# 0123-chips-test-pcb-01.net
KiCad netlist of a schematic drawn in EAGLE
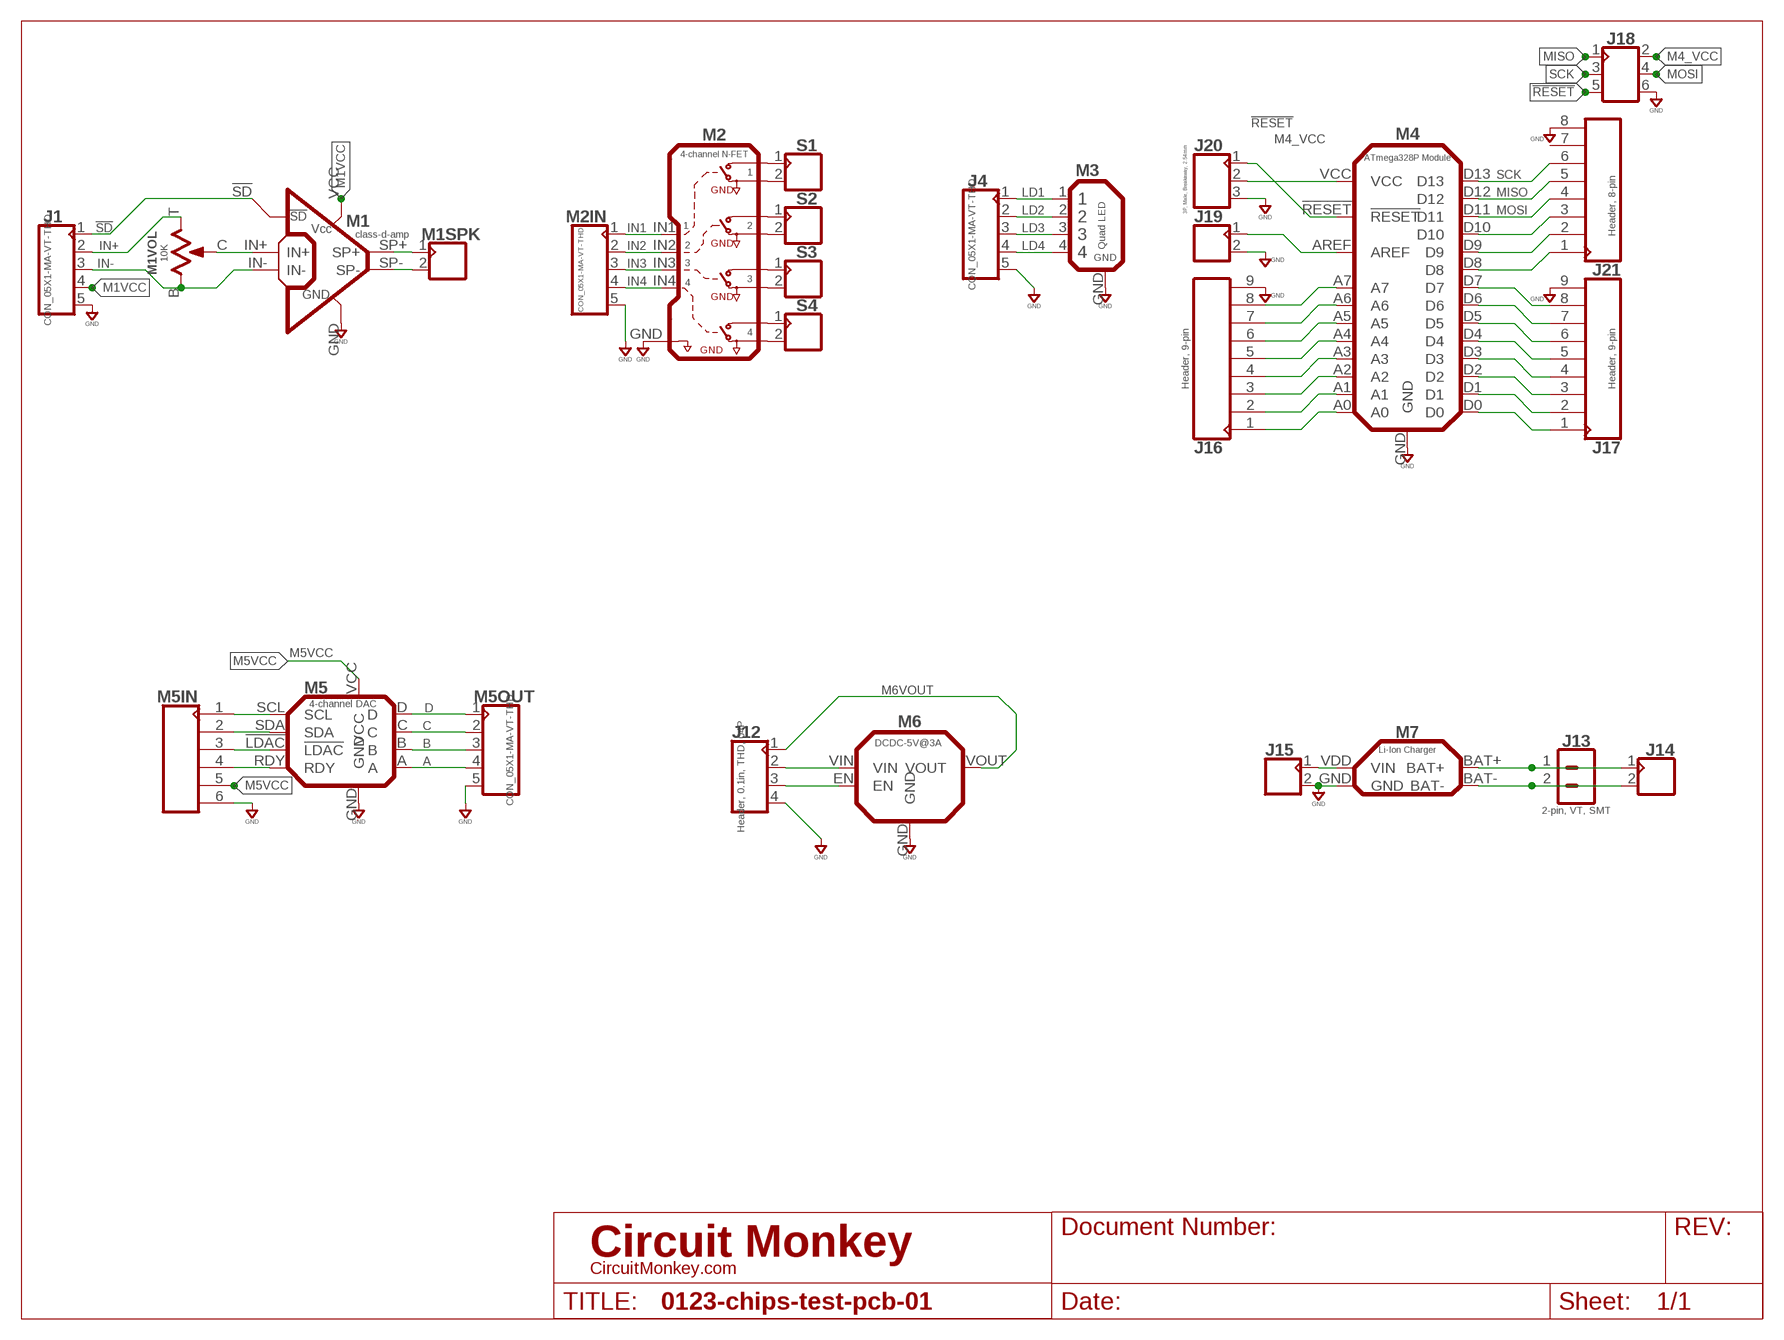
[diagram p0: schematic, sheet 1]

(export (version "E")
  (design (tool "Eeschema 10.0.6"))
  (components
    (comp (ref "J1")
      (value "CON_05X1-MA-VT-THD")
      (footprint "eagle-import:MA05X1-VT-THD")
      (libsource (lib "eagle-import") (part "CON_05X1-MA-VT-THD"))
    )
    (comp (ref "J4")
      (value "CON_05X1-MA-VT-THD")
      (footprint "eagle-import:MA05X1-VT-THD")
      (libsource (lib "eagle-import") (part "CON_05X1-MA-VT-THD"))
    )
    (comp (ref "J12")
      (value "Header, 0.1in, THD, 04P")
      (footprint "eagle-import:MA04X1-VT-THD")
      (fields (field (name "MFR") "Molex") (field (name "MPN") "022284043"))
      (libsource (lib "eagle-import") (part "CON_04X1-THD-VT"))
    )
    (comp (ref "J13")
      (value "2-pin, VT, SMT")
      (footprint "eagle-import:B2B-PH-SM4")
      (fields (field (name "MFR") "JST") (field (name "MPN") "B2B-PH-SM4"))
      (libsource (lib "eagle-import") (part "02PVT-SMT"))
    )
    (comp (ref "J14")
      (value "CON_02X1-2.54MM-THD-VT")
      (footprint "eagle-import:MA02X1-VT-THD")
      (libsource (lib "eagle-import") (part "CON_02X1-2.54MM-THD-VT"))
    )
    (comp (ref "J15")
      (value "CON_02X1-2.54MM-THD-VT")
      (footprint "eagle-import:MA02X1-VT-THD")
      (libsource (lib "eagle-import") (part "CON_02X1-2.54MM-THD-VT"))
    )
    (comp (ref "J16")
      (value "Header, 9-pin")
      (footprint "eagle-import:MA09X1-VT-THD")
      (libsource (lib "eagle-import") (part "CON_09X1-VT-THD"))
    )
    (comp (ref "J17")
      (value "Header, 9-pin")
      (footprint "eagle-import:MA09X1-VT-THD")
      (libsource (lib "eagle-import") (part "CON_09X1-VT-THD"))
    )
    (comp (ref "J18")
      (value "CON_03X2-VT")
      (footprint "eagle-import:MA03X2-VT-THD")
      (libsource (lib "eagle-import") (part "CON_03X2-VT"))
    )
    (comp (ref "J19")
      (value "CON_02X1-2.54MM-THD-VT")
      (footprint "eagle-import:MA02X1-VT-THD")
      (libsource (lib "eagle-import") (part "CON_02X1-2.54MM-THD-VT"))
    )
    (comp (ref "J20")
      (value "3P, Male, Breakaway, 2.54mm")
      (footprint "eagle-import:MA03X1-VT-THD")
      (libsource (lib "eagle-import") (part "CON_03X1-2.54MM-THD-VT"))
    )
    (comp (ref "J21")
      (value "Header, 8-pin")
      (footprint "eagle-import:MA08X1-VT-THD")
      (libsource (lib "eagle-import") (part "CON_08X1-VT-THD"))
    )
    (comp (ref "M1")
      (value "class-d-amp")
      (footprint "eagle-import:0116A")
      (fields (field (name "MFR") "Circuit Monkey") (field (name "MPN") "0116A"))
      (libsource (lib "eagle-import") (part "0116REV-A"))
    )
    (comp (ref "M1SPK")
      (value "CON_02X1-2.54MM-THD-VT")
      (footprint "eagle-import:MA02X1-VT-THD")
      (libsource (lib "eagle-import") (part "CON_02X1-2.54MM-THD-VT"))
    )
    (comp (ref "M1VOL")
      (value "10K")
      (footprint "eagle-import:TRIM_BOURNS_TC33X")
      (fields (field (name "MFR") "Bourns") (field (name "MPN") "TC33X"))
      (libsource (lib "eagle-import") (part "TRIMPOTTC33X"))
    )
    (comp (ref "M2")
      (value "4-channel N-FET")
      (footprint "eagle-import:0117A")
      (fields (field (name "MFR") "Circuit Monkey") (field (name "MPN") "0117A"))
      (libsource (lib "eagle-import") (part "0117REV-A"))
    )
    (comp (ref "M2IN")
      (value "CON_05X1-MA-VT-THD")
      (footprint "eagle-import:MA05X1-VT-THD")
      (libsource (lib "eagle-import") (part "CON_05X1-MA-VT-THD"))
    )
    (comp (ref "M3")
      (value "Quad LED")
      (footprint "eagle-import:0118A")
      (fields (field (name "MFR") "Circuit Monkey") (field (name "MPN") "0118A"))
      (libsource (lib "eagle-import") (part "0118REV-A"))
    )
    (comp (ref "M4")
      (value "ATmega328P Module")
      (footprint "eagle-import:0119A")
      (fields (field (name "MFR") "Circuit Monkey") (field (name "MPN") "0119A"))
      (libsource (lib "eagle-import") (part "0119REV-A"))
    )
    (comp (ref "M5")
      (value "4-channel DAC")
      (footprint "eagle-import:0120A")
      (fields (field (name "MFR") "Circuit Monkey") (field (name "MPN") "0120A"))
      (libsource (lib "eagle-import") (part "0120REV-A"))
    )
    (comp (ref "M5IN")
      (value "CON_06X1-VT")
      (footprint "eagle-import:MA06X1-VT-THD")
      (libsource (lib "eagle-import") (part "CON_06X1-VT"))
    )
    (comp (ref "M5OUT")
      (value "CON_05X1-MA-VT-THD")
      (footprint "eagle-import:MA05X1-VT-THD")
      (libsource (lib "eagle-import") (part "CON_05X1-MA-VT-THD"))
    )
    (comp (ref "M6")
      (value "DCDC-5V@3A")
      (footprint "eagle-import:0121A")
      (fields (field (name "MFR") "Circuit Monkey") (field (name "MPN") "0121A"))
      (libsource (lib "eagle-import") (part "0121REV-A"))
    )
    (comp (ref "M7")
      (value "Li-Ion Charger")
      (footprint "eagle-import:0122A")
      (fields (field (name "MFR") "Circuit Monkey") (field (name "MPN") "0122A"))
      (libsource (lib "eagle-import") (part "0122REV-A"))
    )
    (comp (ref "S1")
      (value "CON_02X1-2.54MM-THD-VT")
      (footprint "eagle-import:MA02X1-VT-THD")
      (libsource (lib "eagle-import") (part "CON_02X1-2.54MM-THD-VT"))
    )
    (comp (ref "S2")
      (value "CON_02X1-2.54MM-THD-VT")
      (footprint "eagle-import:MA02X1-VT-THD")
      (libsource (lib "eagle-import") (part "CON_02X1-2.54MM-THD-VT"))
    )
    (comp (ref "S3")
      (value "CON_02X1-2.54MM-THD-VT")
      (footprint "eagle-import:MA02X1-VT-THD")
      (libsource (lib "eagle-import") (part "CON_02X1-2.54MM-THD-VT"))
    )
    (comp (ref "S4")
      (value "CON_02X1-2.54MM-THD-VT")
      (footprint "eagle-import:MA02X1-VT-THD")
      (libsource (lib "eagle-import") (part "CON_02X1-2.54MM-THD-VT"))
    )
  )
  (nets
    (net (code "1") (name "/A") (class "Default")
      (node (ref "M5") (pin "A") (pinfunction "A_A") (pintype "bidirectional"))
      (node (ref "M5OUT") (pin "4") (pinfunction "4_4") (pintype "passive"))
    )
    (net (code "2") (name "/B") (class "Default")
      (node (ref "M5") (pin "B") (pinfunction "B_B") (pintype "bidirectional"))
      (node (ref "M5OUT") (pin "3") (pinfunction "3_3") (pintype "passive"))
    )
    (net (code "3") (name "/C") (class "Default")
      (node (ref "M5") (pin "C") (pinfunction "C_C") (pintype "bidirectional"))
      (node (ref "M5OUT") (pin "2") (pinfunction "2_2") (pintype "passive"))
    )
    (net (code "4") (name "/D") (class "Default")
      (node (ref "M5") (pin "D") (pinfunction "D_D") (pintype "bidirectional"))
      (node (ref "M5OUT") (pin "1") (pinfunction "1_1") (pintype "passive"))
    )
    (net (code "5") (name "/IN+") (class "Default")
      (node (ref "J1") (pin "2") (pinfunction "2_2") (pintype "passive"))
      (node (ref "M1VOL") (pin "T") (pinfunction "3_T") (pintype "passive"))
    )
    (net (code "6") (name "/IN-") (class "Default")
      (node (ref "J1") (pin "3") (pinfunction "3_3") (pintype "passive"))
      (node (ref "M1") (pin "IN-") (pinfunction "IN-_IN-") (pintype "bidirectional"))
      (node (ref "M1VOL") (pin "B") (pinfunction "1_B") (pintype "passive"))
    )
    (net (code "7") (name "/IN1") (class "Default")
      (node (ref "M2") (pin "IN1") (pinfunction "1_IN1") (pintype "bidirectional"))
      (node (ref "M2IN") (pin "1") (pinfunction "1_1") (pintype "passive"))
    )
    (net (code "8") (name "/IN2") (class "Default")
      (node (ref "M2") (pin "IN2") (pinfunction "2_IN2") (pintype "bidirectional"))
      (node (ref "M2IN") (pin "2") (pinfunction "2_2") (pintype "passive"))
    )
    (net (code "9") (name "/IN3") (class "Default")
      (node (ref "M2") (pin "IN3") (pinfunction "3_IN3") (pintype "bidirectional"))
      (node (ref "M2IN") (pin "3") (pinfunction "3_3") (pintype "passive"))
    )
    (net (code "10") (name "/IN4") (class "Default")
      (node (ref "M2") (pin "IN4") (pinfunction "4_IN4") (pintype "bidirectional"))
      (node (ref "M2IN") (pin "4") (pinfunction "4_4") (pintype "passive"))
    )
    (net (code "11") (name "/LD1") (class "Default")
      (node (ref "J4") (pin "1") (pinfunction "1_1") (pintype "passive"))
      (node (ref "M3") (pin "1") (pinfunction "1_1") (pintype "bidirectional"))
    )
    (net (code "12") (name "/LD2") (class "Default")
      (node (ref "J4") (pin "2") (pinfunction "2_2") (pintype "passive"))
      (node (ref "M3") (pin "2") (pinfunction "2_2") (pintype "bidirectional"))
    )
    (net (code "13") (name "/LD3") (class "Default")
      (node (ref "J4") (pin "3") (pinfunction "3_3") (pintype "passive"))
      (node (ref "M3") (pin "3") (pinfunction "3_3") (pintype "bidirectional"))
    )
    (net (code "14") (name "/LD4") (class "Default")
      (node (ref "J4") (pin "4") (pinfunction "4_4") (pintype "passive"))
      (node (ref "M3") (pin "4") (pinfunction "4_4") (pintype "bidirectional"))
    )
    (net (code "15") (name "/M6VOUT") (class "Default")
      (node (ref "J12") (pin "1") (pinfunction "1_1") (pintype "passive"))
      (node (ref "M6") (pin "VOUT") (pinfunction "VOUT_VOUT") (pintype "bidirectional"))
    )
    (net (code "16") (name "/~{RESET}") (class "Default")
      (node (ref "J18") (pin "5") (pinfunction "5_5") (pintype "passive"))
      (node (ref "J20") (pin "1") (pinfunction "1_1") (pintype "passive"))
      (node (ref "M4") (pin "!RESET") (pinfunction "~{RESET}_!RESET") (pintype "bidirectional"))
    )
    (net (code "17") (name "/~{SD}") (class "Default")
      (node (ref "J1") (pin "1") (pinfunction "1_1") (pintype "passive"))
      (node (ref "M1") (pin "!SD") (pinfunction "~{SD}_!SD") (pintype "bidirectional"))
    )
    (net (code "18") (name "GND") (class "Default")
      (node (ref "J1") (pin "5") (pinfunction "5_5") (pintype "passive"))
      (node (ref "J12") (pin "4") (pinfunction "4_4") (pintype "passive"))
      (node (ref "J15") (pin "2") (pinfunction "2_2") (pintype "passive"))
      (node (ref "J16") (pin "9") (pinfunction "9_9") (pintype "passive"))
      (node (ref "J17") (pin "9") (pinfunction "9_9") (pintype "passive"))
      (node (ref "J18") (pin "6") (pinfunction "6_6") (pintype "passive"))
      (node (ref "J19") (pin "2") (pinfunction "2_2") (pintype "passive"))
      (node (ref "J20") (pin "3") (pinfunction "3_3") (pintype "passive"))
      (node (ref "J21") (pin "8") (pinfunction "8_8") (pintype "passive"))
      (node (ref "J4") (pin "5") (pinfunction "5_5") (pintype "passive"))
      (node (ref "M1") (pin "GND") (pinfunction "GND_GND") (pintype "bidirectional"))
      (node (ref "M2") (pin "GND") (pinfunction "GND_GND") (pintype "bidirectional"))
      (node (ref "M2IN") (pin "5") (pinfunction "5_5") (pintype "passive"))
      (node (ref "M3") (pin "GND") (pinfunction "GND_GND") (pintype "bidirectional"))
      (node (ref "M4") (pin "GND") (pinfunction "GND_GND") (pintype "bidirectional"))
      (node (ref "M5") (pin "GND") (pinfunction "GND_GND") (pintype "bidirectional"))
      (node (ref "M5IN") (pin "6") (pinfunction "6_6") (pintype "passive"))
      (node (ref "M5OUT") (pin "5") (pinfunction "5_5") (pintype "passive"))
      (node (ref "M6") (pin "GND") (pinfunction "GND_GND") (pintype "bidirectional"))
      (node (ref "M7") (pin "GND") (pinfunction "GND_GND") (pintype "bidirectional"))
    )
    (net (code "19") (name "M1VCC") (class "Default")
      (node (ref "J1") (pin "4") (pinfunction "4_4") (pintype "passive"))
      (node (ref "M1") (pin "VCC") (pinfunction "VCC_VCC") (pintype "bidirectional"))
    )
    (net (code "20") (name "M4_VCC") (class "Default")
      (node (ref "J18") (pin "2") (pinfunction "2_2") (pintype "passive"))
      (node (ref "J20") (pin "2") (pinfunction "2_2") (pintype "passive"))
      (node (ref "M4") (pin "VCC") (pinfunction "VCC_VCC") (pintype "bidirectional"))
    )
    (net (code "21") (name "M5VCC") (class "Default")
      (node (ref "M5") (pin "VCC") (pinfunction "VCC_VCC") (pintype "bidirectional"))
      (node (ref "M5IN") (pin "5") (pinfunction "5_5") (pintype "passive"))
    )
    (net (code "22") (name "MISO") (class "Default")
      (node (ref "J18") (pin "1") (pinfunction "1_1") (pintype "passive"))
      (node (ref "J21") (pin "5") (pinfunction "5_5") (pintype "passive"))
      (node (ref "M4") (pin "D12") (pinfunction "D12_D12") (pintype "bidirectional"))
    )
    (net (code "23") (name "MOSI") (class "Default")
      (node (ref "J18") (pin "4") (pinfunction "4_4") (pintype "passive"))
      (node (ref "J21") (pin "4") (pinfunction "4_4") (pintype "passive"))
      (node (ref "M4") (pin "D11") (pinfunction "D11_D11") (pintype "bidirectional"))
    )
    (net (code "24") (name "Net-(J12-Pad2)") (class "Default")
      (node (ref "J12") (pin "2") (pinfunction "2_2") (pintype "passive"))
      (node (ref "M6") (pin "VIN") (pinfunction "VIN_VIN") (pintype "bidirectional"))
    )
    (net (code "25") (name "Net-(J12-Pad3)") (class "Default")
      (node (ref "J12") (pin "3") (pinfunction "3_3") (pintype "passive"))
      (node (ref "M6") (pin "EN") (pinfunction "EN_EN") (pintype "bidirectional"))
    )
    (net (code "26") (name "Net-(J13-Pad1)") (class "Default")
      (node (ref "J13") (pin "1") (pinfunction "1_1") (pintype "passive"))
      (node (ref "J14") (pin "1") (pinfunction "1_1") (pintype "passive"))
      (node (ref "M7") (pin "BAT+") (pinfunction "BAT+_BAT+") (pintype "bidirectional"))
    )
    (net (code "27") (name "Net-(J13-Pad2)") (class "Default")
      (node (ref "J13") (pin "2") (pinfunction "2_2") (pintype "passive"))
      (node (ref "J14") (pin "2") (pinfunction "2_2") (pintype "passive"))
      (node (ref "M7") (pin "BAT-") (pinfunction "BAT-_BAT-") (pintype "bidirectional"))
    )
    (net (code "28") (name "Net-(J16-Pad1)") (class "Default")
      (node (ref "J16") (pin "1") (pinfunction "1_1") (pintype "passive"))
      (node (ref "M4") (pin "A0") (pinfunction "A0_A0") (pintype "bidirectional"))
    )
    (net (code "29") (name "Net-(J16-Pad2)") (class "Default")
      (node (ref "J16") (pin "2") (pinfunction "2_2") (pintype "passive"))
      (node (ref "M4") (pin "A1") (pinfunction "A1_A1") (pintype "bidirectional"))
    )
    (net (code "30") (name "Net-(J16-Pad3)") (class "Default")
      (node (ref "J16") (pin "3") (pinfunction "3_3") (pintype "passive"))
      (node (ref "M4") (pin "A2") (pinfunction "A2_A2") (pintype "bidirectional"))
    )
    (net (code "31") (name "Net-(J16-Pad4)") (class "Default")
      (node (ref "J16") (pin "4") (pinfunction "4_4") (pintype "passive"))
      (node (ref "M4") (pin "A3") (pinfunction "A3_A3") (pintype "bidirectional"))
    )
    (net (code "32") (name "Net-(J16-Pad5)") (class "Default")
      (node (ref "J16") (pin "5") (pinfunction "5_5") (pintype "passive"))
      (node (ref "M4") (pin "A4") (pinfunction "A4_A4") (pintype "bidirectional"))
    )
    (net (code "33") (name "Net-(J16-Pad6)") (class "Default")
      (node (ref "J16") (pin "6") (pinfunction "6_6") (pintype "passive"))
      (node (ref "M4") (pin "A5") (pinfunction "A5_A5") (pintype "bidirectional"))
    )
    (net (code "34") (name "Net-(J16-Pad7)") (class "Default")
      (node (ref "J16") (pin "7") (pinfunction "7_7") (pintype "passive"))
      (node (ref "M4") (pin "A6") (pinfunction "A6_A6") (pintype "bidirectional"))
    )
    (net (code "35") (name "Net-(J16-Pad8)") (class "Default")
      (node (ref "J16") (pin "8") (pinfunction "8_8") (pintype "passive"))
      (node (ref "M4") (pin "A7") (pinfunction "A7_A7") (pintype "bidirectional"))
    )
    (net (code "36") (name "Net-(J17-Pad1)") (class "Default")
      (node (ref "J17") (pin "1") (pinfunction "1_1") (pintype "passive"))
      (node (ref "M4") (pin "D0") (pinfunction "D0_D0") (pintype "bidirectional"))
    )
    (net (code "37") (name "Net-(J17-Pad2)") (class "Default")
      (node (ref "J17") (pin "2") (pinfunction "2_2") (pintype "passive"))
      (node (ref "M4") (pin "D1") (pinfunction "D1_D1") (pintype "bidirectional"))
    )
    (net (code "38") (name "Net-(J17-Pad3)") (class "Default")
      (node (ref "J17") (pin "3") (pinfunction "3_3") (pintype "passive"))
      (node (ref "M4") (pin "D2") (pinfunction "D2_D2") (pintype "bidirectional"))
    )
    (net (code "39") (name "Net-(J17-Pad4)") (class "Default")
      (node (ref "J17") (pin "4") (pinfunction "4_4") (pintype "passive"))
      (node (ref "M4") (pin "D3") (pinfunction "D3_D3") (pintype "bidirectional"))
    )
    (net (code "40") (name "Net-(J17-Pad5)") (class "Default")
      (node (ref "J17") (pin "5") (pinfunction "5_5") (pintype "passive"))
      (node (ref "M4") (pin "D4") (pinfunction "D4_D4") (pintype "bidirectional"))
    )
    (net (code "41") (name "Net-(J17-Pad6)") (class "Default")
      (node (ref "J17") (pin "6") (pinfunction "6_6") (pintype "passive"))
      (node (ref "M4") (pin "D5") (pinfunction "D5_D5") (pintype "bidirectional"))
    )
    (net (code "42") (name "Net-(J17-Pad7)") (class "Default")
      (node (ref "J17") (pin "7") (pinfunction "7_7") (pintype "passive"))
      (node (ref "M4") (pin "D6") (pinfunction "D6_D6") (pintype "bidirectional"))
    )
    (net (code "43") (name "Net-(J17-Pad8)") (class "Default")
      (node (ref "J17") (pin "8") (pinfunction "8_8") (pintype "passive"))
      (node (ref "M4") (pin "D7") (pinfunction "D7_D7") (pintype "bidirectional"))
    )
    (net (code "44") (name "Net-(J19-Pad1)") (class "Default")
      (node (ref "J19") (pin "1") (pinfunction "1_1") (pintype "passive"))
      (node (ref "M4") (pin "AREF") (pinfunction "AREF_AREF") (pintype "bidirectional"))
    )
    (net (code "45") (name "Net-(J21-Pad1)") (class "Default")
      (node (ref "J21") (pin "1") (pinfunction "1_1") (pintype "passive"))
      (node (ref "M4") (pin "D8") (pinfunction "D8_D8") (pintype "bidirectional"))
    )
    (net (code "46") (name "Net-(J21-Pad2)") (class "Default")
      (node (ref "J21") (pin "2") (pinfunction "2_2") (pintype "passive"))
      (node (ref "M4") (pin "D9") (pinfunction "D9_D9") (pintype "bidirectional"))
    )
    (net (code "47") (name "Net-(J21-Pad3)") (class "Default")
      (node (ref "J21") (pin "3") (pinfunction "3_3") (pintype "passive"))
      (node (ref "M4") (pin "D10") (pinfunction "D10_D10") (pintype "bidirectional"))
    )
    (net (code "48") (name "Net-(M1-PadSP+)") (class "Default")
      (node (ref "M1") (pin "SP+") (pinfunction "SP+_SP+") (pintype "bidirectional"))
      (node (ref "M1SPK") (pin "1") (pinfunction "1_1") (pintype "passive"))
    )
    (net (code "49") (name "Net-(M1-PadSP-)") (class "Default")
      (node (ref "M1") (pin "SP-") (pinfunction "SP-_SP-") (pintype "bidirectional"))
      (node (ref "M1SPK") (pin "2") (pinfunction "2_2") (pintype "passive"))
    )
    (net (code "50") (name "Net-(M1VOL-2)") (class "Default")
      (node (ref "M1") (pin "IN+") (pinfunction "IN+_IN+") (pintype "bidirectional"))
      (node (ref "M1VOL") (pin "C") (pinfunction "2_C") (pintype "passive"))
    )
    (net (code "51") (name "Net-(M2-PadGND1)") (class "Default")
      (node (ref "M2") (pin "GND1") (pinfunction "GND1_GND1") (pintype "bidirectional"))
      (node (ref "S1") (pin "2") (pinfunction "2_2") (pintype "passive"))
    )
    (net (code "52") (name "Net-(M2-PadGND2)") (class "Default")
      (node (ref "M2") (pin "GND2") (pinfunction "GND2_GND2") (pintype "bidirectional"))
      (node (ref "S2") (pin "2") (pinfunction "2_2") (pintype "passive"))
    )
    (net (code "53") (name "Net-(M2-PadGND3)") (class "Default")
      (node (ref "M2") (pin "GND3") (pinfunction "GND3_GND3") (pintype "bidirectional"))
      (node (ref "S3") (pin "2") (pinfunction "2_2") (pintype "passive"))
    )
    (net (code "54") (name "Net-(M2-PadGND4)") (class "Default")
      (node (ref "M2") (pin "GND4") (pinfunction "GND4_GND4") (pintype "bidirectional"))
      (node (ref "S4") (pin "2") (pinfunction "2_2") (pintype "passive"))
    )
    (net (code "55") (name "Net-(M2-V1)") (class "Default")
      (node (ref "M2") (pin "OUT1") (pinfunction "V1_OUT1") (pintype "bidirectional"))
      (node (ref "S1") (pin "1") (pinfunction "1_1") (pintype "passive"))
    )
    (net (code "56") (name "Net-(M2-V2)") (class "Default")
      (node (ref "M2") (pin "OUT2") (pinfunction "V2_OUT2") (pintype "bidirectional"))
      (node (ref "S2") (pin "1") (pinfunction "1_1") (pintype "passive"))
    )
    (net (code "57") (name "Net-(M2-V3)") (class "Default")
      (node (ref "M2") (pin "OUT3") (pinfunction "V3_OUT3") (pintype "bidirectional"))
      (node (ref "S3") (pin "1") (pinfunction "1_1") (pintype "passive"))
    )
    (net (code "58") (name "Net-(M2-V4)") (class "Default")
      (node (ref "M2") (pin "OUT4") (pinfunction "V4_OUT4") (pintype "bidirectional"))
      (node (ref "S4") (pin "1") (pinfunction "1_1") (pintype "passive"))
    )
    (net (code "59") (name "Net-(M5-PadRDY)") (class "Default")
      (node (ref "M5") (pin "RDY") (pinfunction "RDY_RDY") (pintype "bidirectional"))
      (node (ref "M5IN") (pin "4") (pinfunction "4_4") (pintype "passive"))
    )
    (net (code "60") (name "Net-(M5-PadSCL)") (class "Default")
      (node (ref "M5") (pin "SCL") (pinfunction "SCL_SCL") (pintype "bidirectional"))
      (node (ref "M5IN") (pin "1") (pinfunction "1_1") (pintype "passive"))
    )
    (net (code "61") (name "Net-(M5-PadSDA)") (class "Default")
      (node (ref "M5") (pin "SDA") (pinfunction "SDA_SDA") (pintype "bidirectional"))
      (node (ref "M5IN") (pin "2") (pinfunction "2_2") (pintype "passive"))
    )
    (net (code "62") (name "Net-(M5-~{LDAC})") (class "Default")
      (node (ref "M5") (pin "!LDAC") (pinfunction "~{LDAC}_!LDAC") (pintype "bidirectional"))
      (node (ref "M5IN") (pin "3") (pinfunction "3_3") (pintype "passive"))
    )
    (net (code "63") (name "Net-(M7-VIN)") (class "Default")
      (node (ref "J15") (pin "1") (pinfunction "1_1") (pintype "passive"))
      (node (ref "M7") (pin "VDD") (pinfunction "VIN_VDD") (pintype "bidirectional"))
    )
    (net (code "64") (name "SCK") (class "Default")
      (node (ref "J18") (pin "3") (pinfunction "3_3") (pintype "passive"))
      (node (ref "J21") (pin "6") (pinfunction "6_6") (pintype "passive"))
      (node (ref "M4") (pin "D13") (pinfunction "D13_D13") (pintype "bidirectional"))
    )
    (net (code "65") (name "unconnected-(J21-Pad7)") (class "Default")
      (node (ref "J21") (pin "7") (pinfunction "7_7") (pintype "passive"))
    )
  )
)
